# TakpadV5.net
KiCad netlist of a schematic drawn in EAGLE
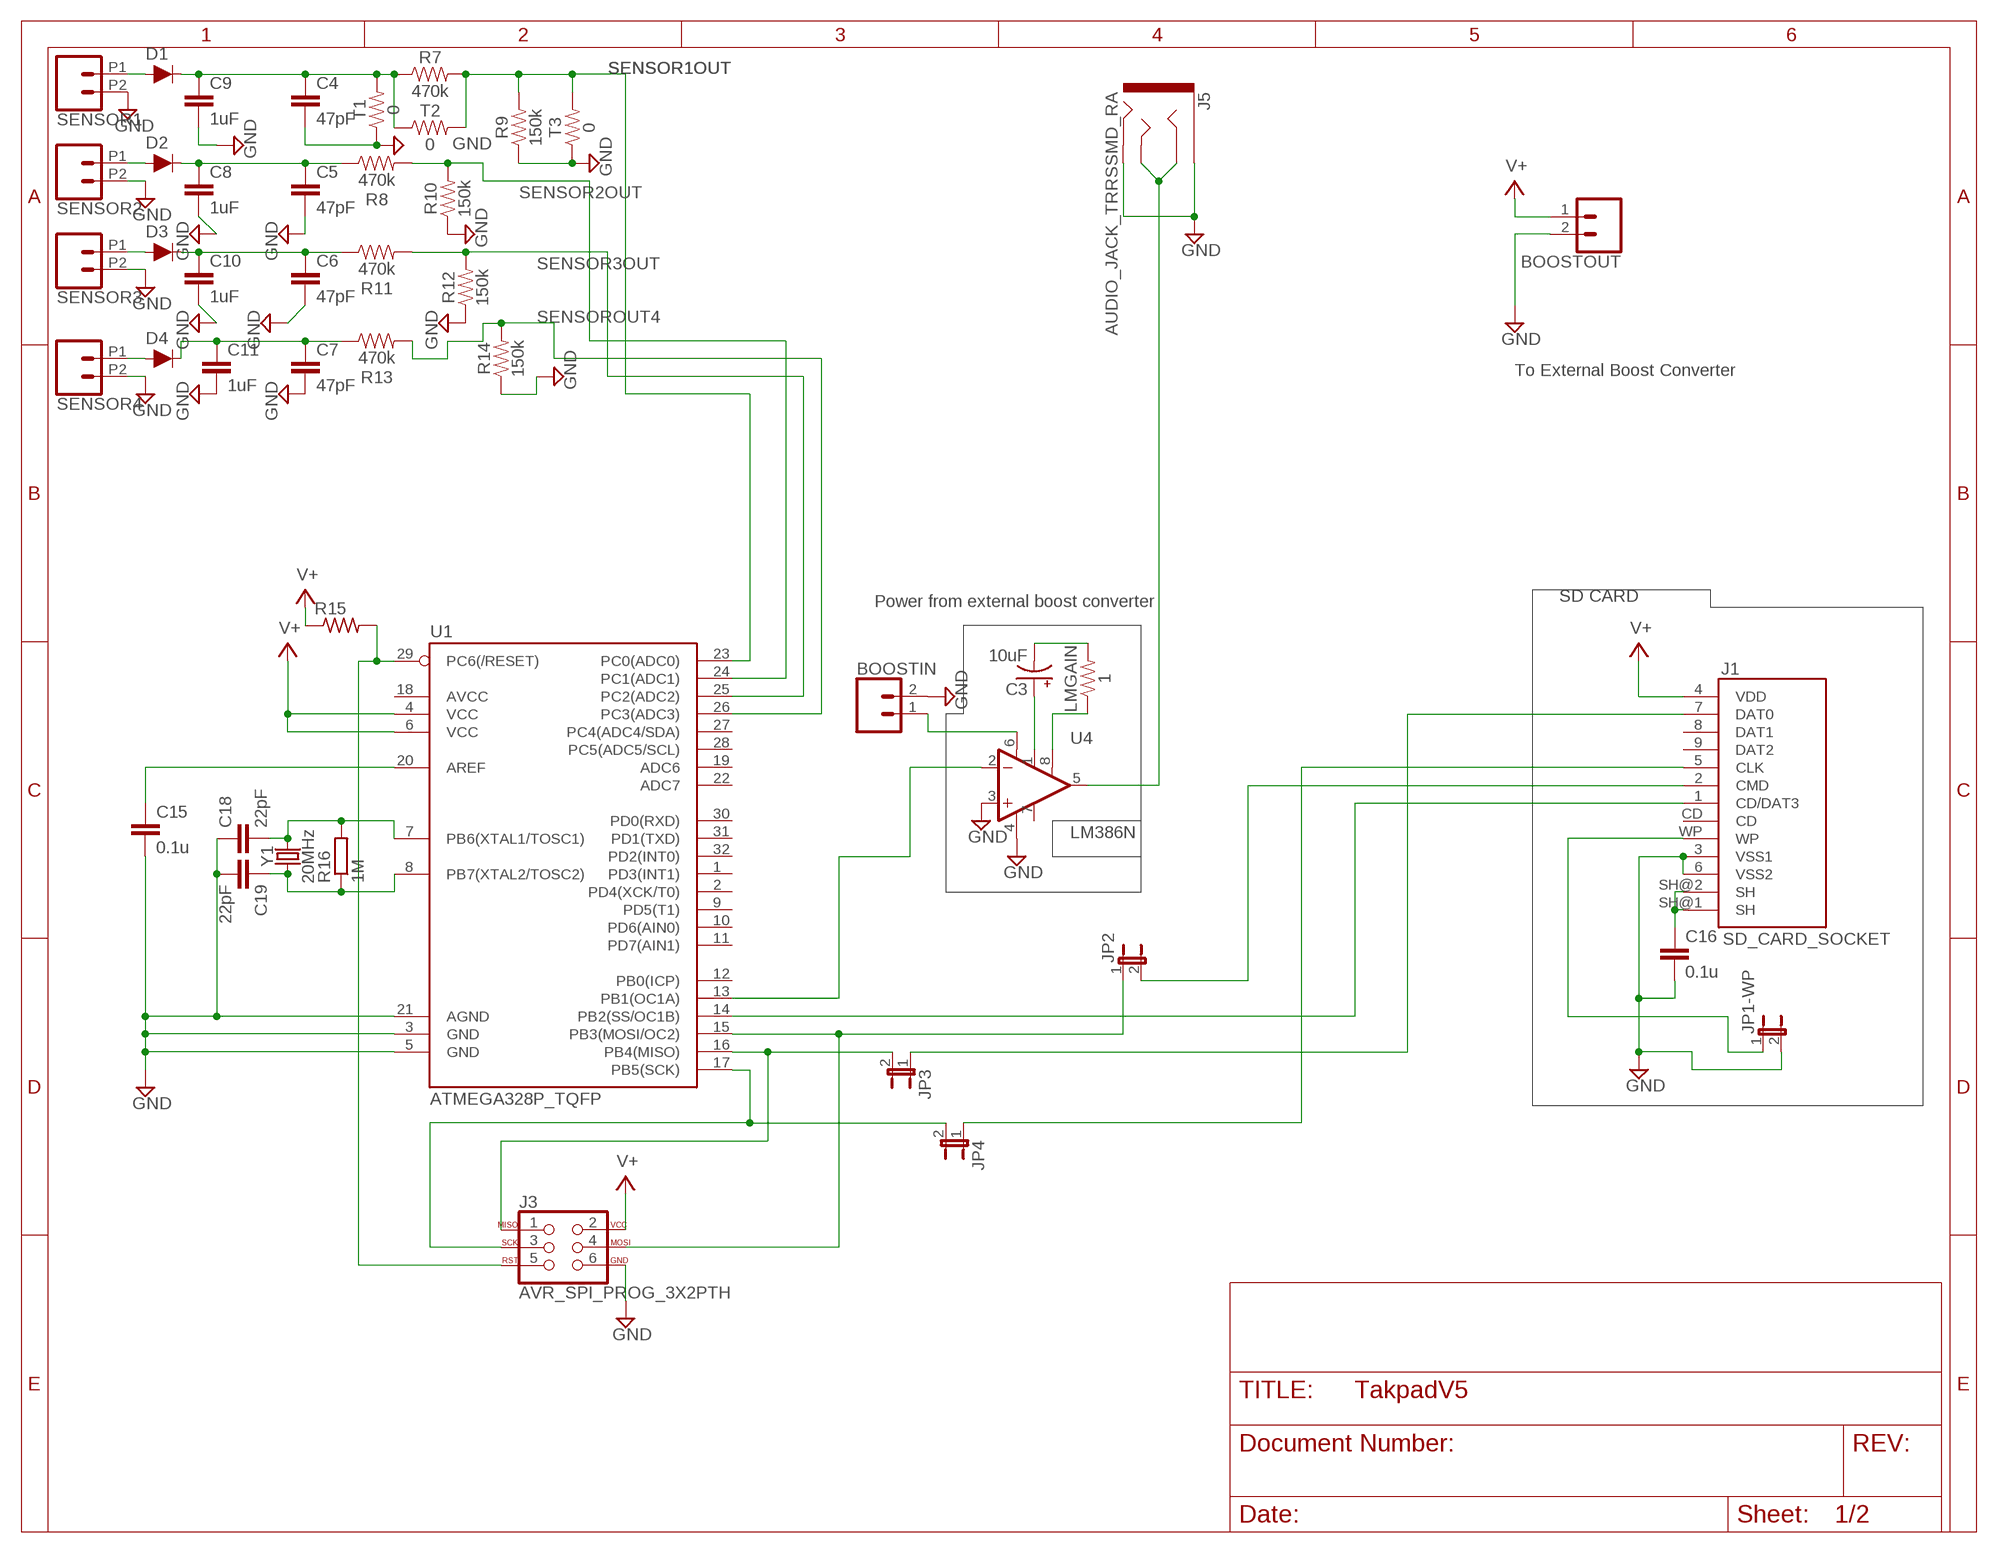
[diagram p0: schematic, sheet 1]
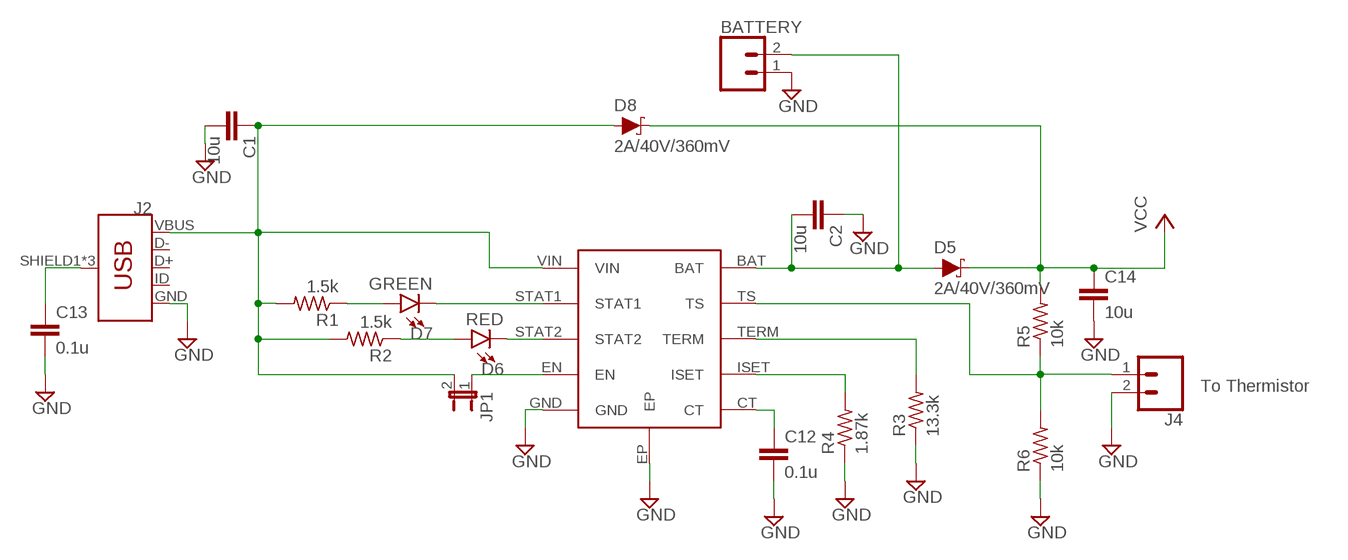
[diagram p1: schematic, sheet 2]

(export (version "E")
  (design (tool "Eeschema 10.0.6"))
  (components
    (comp (ref "BOOSTIN")
      (value "CONN_02")
      (footprint "eagle-import:1X02")
      (libsource (lib "eagle-import") (part "CONN_02"))
    )
    (comp (ref "BOOSTOUT")
      (value "CONN_02")
      (footprint "eagle-import:1X02")
      (libsource (lib "eagle-import") (part "CONN_02"))
    )
    (comp (ref "C3")
      (value "10uF")
      (footprint "eagle-import:CPOL-RADIAL-2.5MM-5MM-KIT")
      (libsource (lib "eagle-import") (part "10UF-POLAR-RADIAL-2.5MM-KIT-25V-20%"))
    )
    (comp (ref "C4")
      (value "47pF")
      (footprint "eagle-import:0603")
      (libsource (lib "eagle-import") (part "47PF-0603-50V-5%"))
    )
    (comp (ref "C5")
      (value "47pF")
      (footprint "eagle-import:0603")
      (libsource (lib "eagle-import") (part "47PF-0603-50V-5%"))
    )
    (comp (ref "C6")
      (value "47pF")
      (footprint "eagle-import:0603")
      (libsource (lib "eagle-import") (part "47PF-0603-50V-5%"))
    )
    (comp (ref "C7")
      (value "47pF")
      (footprint "eagle-import:0603")
      (libsource (lib "eagle-import") (part "47PF-0603-50V-5%"))
    )
    (comp (ref "C8")
      (value "1uF")
      (footprint "eagle-import:0603")
      (libsource (lib "eagle-import") (part "47PF-0603-50V-5%"))
    )
    (comp (ref "C9")
      (value "1uF")
      (footprint "eagle-import:0603")
      (libsource (lib "eagle-import") (part "47PF-0603-50V-5%"))
    )
    (comp (ref "C10")
      (value "1uF")
      (footprint "eagle-import:0603")
      (libsource (lib "eagle-import") (part "47PF-0603-50V-5%"))
    )
    (comp (ref "C11")
      (value "1uF")
      (footprint "eagle-import:0603")
      (libsource (lib "eagle-import") (part "47PF-0603-50V-5%"))
    )
    (comp (ref "C15")
      (value "0.1u")
      (footprint "eagle-import:C0402")
      (libsource (lib "eagle-import") (part "C-EUC0402"))
    )
    (comp (ref "C16")
      (value "0.1u")
      (footprint "eagle-import:C0402")
      (libsource (lib "eagle-import") (part "C-EUC0402"))
    )
    (comp (ref "C18")
      (value "22pF")
      (footprint "eagle-import:C0402")
      (libsource (lib "eagle-import") (part "resistor_348_C-EUC0402"))
    )
    (comp (ref "C19")
      (value "22pF")
      (footprint "eagle-import:C0402")
      (libsource (lib "eagle-import") (part "resistor_348_C-EUC0402"))
    )
    (comp (ref "D1")
      (value "200mA/100V/1V")
      (footprint "eagle-import:DIODE-1N4148")
      (libsource (lib "eagle-import") (part "DIODE-1N4148"))
    )
    (comp (ref "D2")
      (value "200mA/100V/1V")
      (footprint "eagle-import:DIODE-1N4148")
      (libsource (lib "eagle-import") (part "DIODE-1N4148"))
    )
    (comp (ref "D3")
      (value "200mA/100V/1V")
      (footprint "eagle-import:DIODE-1N4148")
      (libsource (lib "eagle-import") (part "DIODE-1N4148"))
    )
    (comp (ref "D4")
      (value "200mA/100V/1V")
      (footprint "eagle-import:DIODE-1N4148")
      (libsource (lib "eagle-import") (part "DIODE-1N4148"))
    )
    (comp (ref "J1")
      (value "SD_CARD_SOCKET")
      (footprint "eagle-import:SD")
      (libsource (lib "eagle-import") (part "SD_CARD_SOCKET"))
    )
    (comp (ref "J3")
      (value "AVR_SPI_PROG_3X2PTH")
      (footprint "eagle-import:2X3")
      (libsource (lib "eagle-import") (part "AVR_SPI_PROG_3X2PTH"))
    )
    (comp (ref "J5")
      (value "AUDIO_JACK_TRRSSMD_RA")
      (footprint "eagle-import:AUDIO_JACK_3.5MM_TRRS_SMD_RA")
      (fields (field (name "SPICEPREFIX") "E"))
      (libsource (lib "eagle-import") (part "AUDIO_JACK_TRRSSMD_RA"))
    )
    (comp (ref "JP1-WP")
      (value "JUMPER-2PTH")
      (footprint "eagle-import:1X02")
      (libsource (lib "eagle-import") (part "JUMPER-2PTH"))
    )
    (comp (ref "JP2")
      (value "JUMPER-2PTH")
      (footprint "eagle-import:1X02")
      (libsource (lib "eagle-import") (part "JUMPER-2PTH"))
    )
    (comp (ref "JP3")
      (value "JUMPER-2PTH")
      (footprint "eagle-import:1X02")
      (libsource (lib "eagle-import") (part "JUMPER-2PTH"))
    )
    (comp (ref "JP4")
      (value "JUMPER-2PTH")
      (footprint "eagle-import:1X02")
      (libsource (lib "eagle-import") (part "JUMPER-2PTH"))
    )
    (comp (ref "LMGAIN")
      (value "1")
      (footprint "eagle-import:0603")
      (libsource (lib "eagle-import") (part "1OHM-0603-1/10W-1%"))
    )
    (comp (ref "R7")
      (value "470k")
      (footprint "eagle-import:AXIAL-0.3")
      (libsource (lib "eagle-import") (part "1KOHM-HORIZ-1/4W-1%"))
    )
    (comp (ref "R8")
      (value "470k")
      (footprint "eagle-import:AXIAL-0.3")
      (libsource (lib "eagle-import") (part "1KOHM-HORIZ-1/4W-1%"))
    )
    (comp (ref "R9")
      (value "150k")
      (footprint "eagle-import:AXIAL-0.3")
      (libsource (lib "eagle-import") (part "1KOHM-HORIZ-1/4W-1%"))
    )
    (comp (ref "R10")
      (value "150k")
      (footprint "eagle-import:AXIAL-0.3")
      (libsource (lib "eagle-import") (part "1KOHM-HORIZ-1/4W-1%"))
    )
    (comp (ref "R11")
      (value "470k")
      (footprint "eagle-import:AXIAL-0.3")
      (libsource (lib "eagle-import") (part "1KOHM-HORIZ-1/4W-1%"))
    )
    (comp (ref "R12")
      (value "150k")
      (footprint "eagle-import:AXIAL-0.3")
      (libsource (lib "eagle-import") (part "1KOHM-HORIZ-1/4W-1%"))
    )
    (comp (ref "R13")
      (value "470k")
      (footprint "eagle-import:AXIAL-0.3")
      (libsource (lib "eagle-import") (part "1KOHM-HORIZ-1/4W-1%"))
    )
    (comp (ref "R14")
      (value "150k")
      (footprint "eagle-import:AXIAL-0.3")
      (libsource (lib "eagle-import") (part "1KOHM-HORIZ-1/4W-1%"))
    )
    (comp (ref "R15")
      (value "R-US_M1206")
      (footprint "eagle-import:M1206")
      (libsource (lib "eagle-import") (part "R-US_M1206"))
    )
    (comp (ref "R16")
      (value "1M")
      (footprint "eagle-import:R0402")
      (libsource (lib "eagle-import") (part "R-EU_R0402"))
    )
    (comp (ref "SENSOR1")
      (value "CONN_022.54MM_SCREWTERM")
      (footprint "eagle-import:1X02_2.54_SCREWTERM")
      (libsource (lib "eagle-import") (part "CONN_022.54MM_SCREWTERM"))
    )
    (comp (ref "SENSOR2")
      (value "CONN_022.54MM_SCREWTERM")
      (footprint "eagle-import:1X02_2.54_SCREWTERM")
      (libsource (lib "eagle-import") (part "CONN_022.54MM_SCREWTERM"))
    )
    (comp (ref "SENSOR3")
      (value "CONN_022.54MM_SCREWTERM")
      (footprint "eagle-import:1X02_2.54_SCREWTERM")
      (libsource (lib "eagle-import") (part "CONN_022.54MM_SCREWTERM"))
    )
    (comp (ref "SENSOR4")
      (value "CONN_022.54MM_SCREWTERM")
      (footprint "eagle-import:1X02_2.54_SCREWTERM")
      (libsource (lib "eagle-import") (part "CONN_022.54MM_SCREWTERM"))
    )
    (comp (ref "T1")
      (value "0")
      (footprint "eagle-import:AXIAL-0.3")
      (libsource (lib "eagle-import") (part "1KOHM-HORIZ-1/4W-1%"))
    )
    (comp (ref "T2")
      (value "0")
      (footprint "eagle-import:AXIAL-0.3")
      (libsource (lib "eagle-import") (part "1KOHM-HORIZ-1/4W-1%"))
    )
    (comp (ref "T3")
      (value "0")
      (footprint "eagle-import:AXIAL-0.3")
      (libsource (lib "eagle-import") (part "1KOHM-HORIZ-1/4W-1%"))
    )
    (comp (ref "U1")
      (value "ATMEGA328P_TQFP")
      (footprint "eagle-import:TQFP32-08")
      (libsource (lib "eagle-import") (part "ATMEGA328P_TQFP"))
    )
    (comp (ref "U4")
      (value "LM386N")
      (footprint "eagle-import:DIP08")
      (libsource (lib "eagle-import") (part "LM386"))
    )
    (comp (ref "Y1")
      (value "20MHz")
      (footprint "eagle-import:HC49US")
      (libsource (lib "eagle-import") (part "CRYSTAL-16MHZPTH-HC49US"))
    )
    (comp (ref "BATTERY")
      (value "CONN_02")
      (footprint "eagle-import:1X02")
      (libsource (lib "eagle-import") (part "CONN_02"))
    )
    (comp (ref "C1")
      (value "10u")
      (footprint "eagle-import:C025-024X044")
      (libsource (lib "eagle-import") (part "C-EU025-024X044"))
    )
    (comp (ref "C2")
      (value "10u")
      (footprint "eagle-import:C025-024X044")
      (libsource (lib "eagle-import") (part "C-EU025-024X044"))
    )
    (comp (ref "C12")
      (value "0.1u")
      (footprint "eagle-import:C0402")
      (libsource (lib "eagle-import") (part "C-EUC0402"))
    )
    (comp (ref "C13")
      (value "0.1u")
      (footprint "eagle-import:C0402")
      (libsource (lib "eagle-import") (part "C-EUC0402"))
    )
    (comp (ref "C14")
      (value "10u")
      (footprint "eagle-import:C025-024X044")
      (libsource (lib "eagle-import") (part "C-EU025-024X044"))
    )
    (comp (ref "D5")
      (value "2A/40V/360mV")
      (footprint "eagle-import:SMA-DIODE")
      (libsource (lib "eagle-import") (part "DIODE-SCHOTTKY-B340A"))
    )
    (comp (ref "D6")
      (value "RED")
      (footprint "eagle-import:LED-1206")
      (libsource (lib "eagle-import") (part "LED-RED1206"))
    )
    (comp (ref "D7")
      (value "GREEN")
      (footprint "eagle-import:LED-1206")
      (libsource (lib "eagle-import") (part "LED-GREEN1206"))
    )
    (comp (ref "D8")
      (value "2A/40V/360mV")
      (footprint "eagle-import:SMA-DIODE")
      (libsource (lib "eagle-import") (part "DIODE-SCHOTTKY-B340A"))
    )
    (comp (ref "J2")
      (value "USB_MICRO-BREDUCED_PASTE")
      (footprint "eagle-import:USB-B-MICRO-SMD_RED_PASTE")
      (libsource (lib "eagle-import") (part "USB_MICRO-BREDUCED_PASTE"))
    )
    (comp (ref "J4")
      (value "CONN_02")
      (footprint "eagle-import:1X02")
      (libsource (lib "eagle-import") (part "CONN_02"))
    )
    (comp (ref "JP1")
      (value "JUMPER-2PTH")
      (footprint "eagle-import:1X02")
      (libsource (lib "eagle-import") (part "JUMPER-2PTH"))
    )
    (comp (ref "R1")
      (value "1.5k")
      (footprint "eagle-import:M1206")
      (libsource (lib "eagle-import") (part "R-US_M1206"))
    )
    (comp (ref "R2")
      (value "1.5k")
      (footprint "eagle-import:M1206")
      (libsource (lib "eagle-import") (part "R-US_M1206"))
    )
    (comp (ref "R3")
      (value "13.3k")
      (footprint "eagle-import:M1206")
      (libsource (lib "eagle-import") (part "R-US_M1206"))
    )
    (comp (ref "R4")
      (value "1.87k")
      (footprint "eagle-import:M1206")
      (libsource (lib "eagle-import") (part "R-US_M1206"))
    )
    (comp (ref "R5")
      (value "10k")
      (footprint "eagle-import:M1206")
      (libsource (lib "eagle-import") (part "R-US_M1206"))
    )
    (comp (ref "R6")
      (value "10k")
      (footprint "eagle-import:M1206")
      (libsource (lib "eagle-import") (part "R-US_M1206"))
    )
    (comp (ref "U$1")
      (value "AAT3693")
      (footprint "eagle-import:IDH-AA-T1")
      (libsource (lib "eagle-import") (part "AAT3693"))
    )
  )
  (nets
    (net (code "1") (name "GND") (class "Default")
      (node (ref "BATTERY") (pin "1") (pinfunction "1_1") (pintype "passive"))
      (node (ref "BOOSTIN") (pin "2") (pinfunction "2_2") (pintype "passive"))
      (node (ref "BOOSTOUT") (pin "2") (pinfunction "2_2") (pintype "passive"))
      (node (ref "C1") (pin "2") (pinfunction "2_2") (pintype "passive"))
      (node (ref "C10") (pin "2") (pinfunction "2_2") (pintype "passive"))
      (node (ref "C11") (pin "2") (pinfunction "2_2") (pintype "passive"))
      (node (ref "C12") (pin "2") (pinfunction "2_2") (pintype "passive"))
      (node (ref "C13") (pin "2") (pinfunction "2_2") (pintype "passive"))
      (node (ref "C14") (pin "2") (pinfunction "2_2") (pintype "passive"))
      (node (ref "C15") (pin "2") (pinfunction "2_2") (pintype "passive"))
      (node (ref "C16") (pin "2") (pinfunction "2_2") (pintype "passive"))
      (node (ref "C18") (pin "1") (pinfunction "1_1") (pintype "passive"))
      (node (ref "C19") (pin "2") (pinfunction "2_2") (pintype "passive"))
      (node (ref "C2") (pin "1") (pinfunction "1_1") (pintype "passive"))
      (node (ref "C4") (pin "2") (pinfunction "2_2") (pintype "passive"))
      (node (ref "C5") (pin "2") (pinfunction "2_2") (pintype "passive"))
      (node (ref "C6") (pin "2") (pinfunction "2_2") (pintype "passive"))
      (node (ref "C7") (pin "2") (pinfunction "2_2") (pintype "passive"))
      (node (ref "C8") (pin "2") (pinfunction "2_2") (pintype "passive"))
      (node (ref "C9") (pin "2") (pinfunction "2_2") (pintype "passive"))
      (node (ref "J1") (pin "3") (pinfunction "VSS1_3") (pintype "power_in"))
      (node (ref "J1") (pin "6") (pinfunction "VSS2_6") (pintype "power_in"))
      (node (ref "J2") (pin "GND") (pinfunction "GND_GND") (pintype "power_in"))
      (node (ref "J3") (pin "6") (pinfunction "6_6") (pintype "passive"))
      (node (ref "J4") (pin "2") (pinfunction "2_2") (pintype "passive"))
      (node (ref "J5") (pin "EARTH") (pinfunction "EARTH_EARTH") (pintype "bidirectional"))
      (node (ref "J5") (pin "RING2") (pinfunction "RING2_RING2") (pintype "bidirectional"))
      (node (ref "JP1-WP") (pin "2") (pinfunction "2_2") (pintype "passive"))
      (node (ref "R10") (pin "P$1") (pinfunction "1_P$1") (pintype "passive"))
      (node (ref "R12") (pin "P$1") (pinfunction "1_P$1") (pintype "passive"))
      (node (ref "R14") (pin "P$1") (pinfunction "1_P$1") (pintype "passive"))
      (node (ref "R3") (pin "1") (pinfunction "1_1") (pintype "passive"))
      (node (ref "R4") (pin "1") (pinfunction "1_1") (pintype "passive"))
      (node (ref "R6") (pin "1") (pinfunction "1_1") (pintype "passive"))
      (node (ref "R9") (pin "P$1") (pinfunction "1_P$1") (pintype "passive"))
      (node (ref "SENSOR1") (pin "P2") (pinfunction "2_P2") (pintype "passive"))
      (node (ref "SENSOR2") (pin "P2") (pinfunction "2_P2") (pintype "passive"))
      (node (ref "SENSOR3") (pin "P2") (pinfunction "2_P2") (pintype "passive"))
      (node (ref "SENSOR4") (pin "P2") (pinfunction "2_P2") (pintype "passive"))
      (node (ref "T1") (pin "P$1") (pinfunction "1_P$1") (pintype "passive"))
      (node (ref "T3") (pin "P$1") (pinfunction "1_P$1") (pintype "passive"))
      (node (ref "U$1") (pin "EP") (pinfunction "EP_EP") (pintype "bidirectional"))
      (node (ref "U$1") (pin "GND") (pinfunction "GND_GND") (pintype "bidirectional"))
      (node (ref "U1") (pin "21") (pinfunction "AGND_21") (pintype "bidirectional"))
      (node (ref "U1") (pin "3") (pinfunction "GND_3") (pintype "bidirectional"))
      (node (ref "U1") (pin "5") (pinfunction "GND_5") (pintype "bidirectional"))
      (node (ref "U4") (pin "3") (pinfunction "+IN_3") (pintype "input"))
      (node (ref "U4") (pin "4") (pinfunction "V-_4") (pintype "power_in"))
    )
    (net (code "2") (name "Net-(BATTERY-Pad2)") (class "Default")
      (node (ref "BATTERY") (pin "2") (pinfunction "2_2") (pintype "passive"))
      (node (ref "C2") (pin "2") (pinfunction "2_2") (pintype "passive"))
      (node (ref "D5") (pin "A") (pinfunction "A_A") (pintype "passive"))
      (node (ref "U$1") (pin "BAT") (pinfunction "BAT_BAT") (pintype "bidirectional"))
    )
    (net (code "3") (name "Net-(C1-Pad1)") (class "Default")
      (node (ref "C1") (pin "1") (pinfunction "1_1") (pintype "passive"))
      (node (ref "D8") (pin "A") (pinfunction "A_A") (pintype "passive"))
      (node (ref "J2") (pin "VBUS") (pinfunction "VBUS_VBUS") (pintype "power_in"))
      (node (ref "JP1") (pin "2") (pinfunction "2_2") (pintype "passive"))
      (node (ref "R1") (pin "2") (pinfunction "2_2") (pintype "passive"))
      (node (ref "R2") (pin "2") (pinfunction "2_2") (pintype "passive"))
      (node (ref "U$1") (pin "VIN") (pinfunction "VIN_VIN") (pintype "bidirectional"))
    )
    (net (code "4") (name "Net-(C3-+)") (class "Default")
      (node (ref "C3") (pin "1") (pinfunction "+_1") (pintype "passive"))
      (node (ref "U4") (pin "1") (pinfunction "GAIN_1") (pintype "bidirectional"))
    )
    (net (code "5") (name "Net-(C3--)") (class "Default")
      (node (ref "C3") (pin "2") (pinfunction "-_2") (pintype "passive"))
      (node (ref "LMGAIN") (pin "2") (pinfunction "2_2") (pintype "passive"))
    )
    (net (code "6") (name "Net-(C12-Pad1)") (class "Default")
      (node (ref "C12") (pin "1") (pinfunction "1_1") (pintype "passive"))
      (node (ref "U$1") (pin "CT") (pinfunction "CT_CT") (pintype "bidirectional"))
    )
    (net (code "7") (name "Net-(C13-Pad1)") (class "Default")
      (node (ref "C13") (pin "1") (pinfunction "1_1") (pintype "passive"))
      (node (ref "J2") (pin "SHIELD1") (pinfunction "SHIELD_SHIELD1") (pintype "bidirectional"))
      (node (ref "J2") (pin "SHIELD2") (pinfunction "SHIELD_SHIELD2") (pintype "bidirectional"))
      (node (ref "J2") (pin "SHIELD3") (pinfunction "SHIELD_SHIELD3") (pintype "bidirectional"))
    )
    (net (code "8") (name "Net-(C16-Pad1)") (class "Default")
      (node (ref "C16") (pin "1") (pinfunction "1_1") (pintype "passive"))
      (node (ref "J1") (pin "SH@1") (pinfunction "SH_SH@1") (pintype "bidirectional"))
      (node (ref "J1") (pin "SH@2") (pinfunction "SH_SH@2") (pintype "bidirectional"))
    )
    (net (code "9") (name "Net-(D6-PadA)") (class "Default")
      (node (ref "D6") (pin "A") (pinfunction "A_A") (pintype "passive"))
      (node (ref "R2") (pin "1") (pinfunction "1_1") (pintype "passive"))
    )
    (net (code "10") (name "Net-(D6-PadC)") (class "Default")
      (node (ref "D6") (pin "C") (pinfunction "C_C") (pintype "passive"))
      (node (ref "U$1") (pin "STAT2") (pinfunction "STAT2_STAT2") (pintype "bidirectional"))
    )
    (net (code "11") (name "Net-(D7-PadA)") (class "Default")
      (node (ref "D7") (pin "A") (pinfunction "A_A") (pintype "passive"))
      (node (ref "R1") (pin "1") (pinfunction "1_1") (pintype "passive"))
    )
    (net (code "12") (name "Net-(D7-PadC)") (class "Default")
      (node (ref "D7") (pin "C") (pinfunction "C_C") (pintype "passive"))
      (node (ref "U$1") (pin "STAT1") (pinfunction "STAT1_STAT1") (pintype "bidirectional"))
    )
    (net (code "13") (name "Net-(J1-CD{slash}DAT3)") (class "Default")
      (node (ref "J1") (pin "1") (pinfunction "CD/DAT3_1") (pintype "bidirectional"))
      (node (ref "U1") (pin "14") (pinfunction "PB2(SS/OC1B)_14") (pintype "bidirectional"))
    )
    (net (code "14") (name "Net-(J1-CLK)") (class "Default")
      (node (ref "J1") (pin "5") (pinfunction "CLK_5") (pintype "bidirectional"))
      (node (ref "JP4") (pin "1") (pinfunction "1_1") (pintype "passive"))
    )
    (net (code "15") (name "Net-(J1-CMD)") (class "Default")
      (node (ref "J1") (pin "2") (pinfunction "CMD_2") (pintype "bidirectional"))
      (node (ref "JP2") (pin "2") (pinfunction "2_2") (pintype "passive"))
    )
    (net (code "16") (name "Net-(J1-DAT0)") (class "Default")
      (node (ref "J1") (pin "7") (pinfunction "DAT0_7") (pintype "bidirectional"))
      (node (ref "JP3") (pin "1") (pinfunction "1_1") (pintype "passive"))
    )
    (net (code "17") (name "Net-(J1-PadWP)") (class "Default")
      (node (ref "J1") (pin "WP") (pinfunction "WP_WP") (pintype "bidirectional"))
      (node (ref "JP1-WP") (pin "1") (pinfunction "1_1") (pintype "passive"))
    )
    (net (code "18") (name "Net-(J4-Pad1)") (class "Default")
      (node (ref "J4") (pin "1") (pinfunction "1_1") (pintype "passive"))
      (node (ref "R5") (pin "1") (pinfunction "1_1") (pintype "passive"))
      (node (ref "R6") (pin "2") (pinfunction "2_2") (pintype "passive"))
      (node (ref "U$1") (pin "TS") (pinfunction "TS_TS") (pintype "bidirectional"))
    )
    (net (code "19") (name "Net-(JP1-Pad1)") (class "Default")
      (node (ref "JP1") (pin "1") (pinfunction "1_1") (pintype "passive"))
      (node (ref "U$1") (pin "EN") (pinfunction "EN_EN") (pintype "bidirectional"))
    )
    (net (code "20") (name "Net-(LMGAIN-Pad1)") (class "Default")
      (node (ref "LMGAIN") (pin "1") (pinfunction "1_1") (pintype "passive"))
      (node (ref "U4") (pin "8") (pinfunction "GAIN_8") (pintype "bidirectional"))
    )
    (net (code "21") (name "Net-(R3-Pad2)") (class "Default")
      (node (ref "R3") (pin "2") (pinfunction "2_2") (pintype "passive"))
      (node (ref "U$1") (pin "TERM") (pinfunction "TERM_TERM") (pintype "bidirectional"))
    )
    (net (code "22") (name "Net-(R4-Pad2)") (class "Default")
      (node (ref "R4") (pin "2") (pinfunction "2_2") (pintype "passive"))
      (node (ref "U$1") (pin "ISET") (pinfunction "ISET_ISET") (pintype "bidirectional"))
    )
    (net (code "23") (name "Net-(R7-1)") (class "Default")
      (node (ref "C4") (pin "1") (pinfunction "1_1") (pintype "passive"))
      (node (ref "C9") (pin "1") (pinfunction "1_1") (pintype "passive"))
      (node (ref "D1") (pin "C") (pinfunction "C_C") (pintype "passive"))
      (node (ref "R7") (pin "P$1") (pinfunction "1_P$1") (pintype "passive"))
      (node (ref "T1") (pin "P$2") (pinfunction "2_P$2") (pintype "passive"))
      (node (ref "T2") (pin "P$1") (pinfunction "1_P$1") (pintype "passive"))
    )
    (net (code "24") (name "Net-(R8-1)") (class "Default")
      (node (ref "C5") (pin "1") (pinfunction "1_1") (pintype "passive"))
      (node (ref "C8") (pin "1") (pinfunction "1_1") (pintype "passive"))
      (node (ref "D2") (pin "C") (pinfunction "C_C") (pintype "passive"))
      (node (ref "R8") (pin "P$1") (pinfunction "1_P$1") (pintype "passive"))
    )
    (net (code "25") (name "Net-(R11-1)") (class "Default")
      (node (ref "C10") (pin "1") (pinfunction "1_1") (pintype "passive"))
      (node (ref "C6") (pin "1") (pinfunction "1_1") (pintype "passive"))
      (node (ref "D3") (pin "C") (pinfunction "C_C") (pintype "passive"))
      (node (ref "R11") (pin "P$1") (pinfunction "1_P$1") (pintype "passive"))
    )
    (net (code "26") (name "Net-(R13-1)") (class "Default")
      (node (ref "C11") (pin "1") (pinfunction "1_1") (pintype "passive"))
      (node (ref "C7") (pin "1") (pinfunction "1_1") (pintype "passive"))
      (node (ref "D4") (pin "C") (pinfunction "C_C") (pintype "passive"))
      (node (ref "R13") (pin "P$1") (pinfunction "1_P$1") (pintype "passive"))
    )
    (net (code "27") (name "Net-(SENSOR1-1)") (class "Default")
      (node (ref "D1") (pin "A") (pinfunction "A_A") (pintype "passive"))
      (node (ref "SENSOR1") (pin "P1") (pinfunction "1_P1") (pintype "passive"))
    )
    (net (code "28") (name "Net-(SENSOR2-1)") (class "Default")
      (node (ref "D2") (pin "A") (pinfunction "A_A") (pintype "passive"))
      (node (ref "SENSOR2") (pin "P1") (pinfunction "1_P1") (pintype "passive"))
    )
    (net (code "29") (name "Net-(SENSOR3-1)") (class "Default")
      (node (ref "D3") (pin "A") (pinfunction "A_A") (pintype "passive"))
      (node (ref "SENSOR3") (pin "P1") (pinfunction "1_P1") (pintype "passive"))
    )
    (net (code "30") (name "Net-(SENSOR4-1)") (class "Default")
      (node (ref "D4") (pin "A") (pinfunction "A_A") (pintype "passive"))
      (node (ref "SENSOR4") (pin "P1") (pinfunction "1_P1") (pintype "passive"))
    )
    (net (code "31") (name "Net-(U1-AREF)") (class "Default")
      (node (ref "C15") (pin "1") (pinfunction "1_1") (pintype "passive"))
      (node (ref "U1") (pin "20") (pinfunction "AREF_20") (pintype "bidirectional"))
    )
    (net (code "32") (name "Net-(U1-PB1(OC1A))") (class "Default")
      (node (ref "U1") (pin "13") (pinfunction "PB1(OC1A)_13") (pintype "bidirectional"))
      (node (ref "U4") (pin "2") (pinfunction "-IN_2") (pintype "input"))
    )
    (net (code "33") (name "Net-(U1-PB3(MOSI{slash}OC2))") (class "Default")
      (node (ref "J3") (pin "4") (pinfunction "4_4") (pintype "passive"))
      (node (ref "JP2") (pin "1") (pinfunction "1_1") (pintype "passive"))
      (node (ref "U1") (pin "15") (pinfunction "PB3(MOSI/OC2)_15") (pintype "bidirectional"))
    )
    (net (code "34") (name "Net-(U1-PB4(MISO))") (class "Default")
      (node (ref "J3") (pin "1") (pinfunction "1_1") (pintype "passive"))
      (node (ref "JP3") (pin "2") (pinfunction "2_2") (pintype "passive"))
      (node (ref "U1") (pin "16") (pinfunction "PB4(MISO)_16") (pintype "bidirectional"))
    )
    (net (code "35") (name "Net-(U1-PB5(SCK))") (class "Default")
      (node (ref "J3") (pin "3") (pinfunction "3_3") (pintype "passive"))
      (node (ref "JP4") (pin "2") (pinfunction "2_2") (pintype "passive"))
      (node (ref "U1") (pin "17") (pinfunction "PB5(SCK)_17") (pintype "bidirectional"))
    )
    (net (code "36") (name "Net-(U1-PB6(XTAL1{slash}TOSC1))") (class "Default")
      (node (ref "C18") (pin "2") (pinfunction "2_2") (pintype "passive"))
      (node (ref "R16") (pin "2") (pinfunction "2_2") (pintype "passive"))
      (node (ref "U1") (pin "7") (pinfunction "PB6(XTAL1/TOSC1)_7") (pintype "bidirectional"))
      (node (ref "Y1") (pin "2") (pinfunction "2_2") (pintype "passive"))
    )
    (net (code "37") (name "Net-(U1-PB7(XTAL2{slash}TOSC2))") (class "Default")
      (node (ref "C19") (pin "1") (pinfunction "1_1") (pintype "passive"))
      (node (ref "R16") (pin "1") (pinfunction "1_1") (pintype "passive"))
      (node (ref "U1") (pin "8") (pinfunction "PB7(XTAL2/TOSC2)_8") (pintype "bidirectional"))
      (node (ref "Y1") (pin "1") (pinfunction "1_1") (pintype "passive"))
    )
    (net (code "38") (name "Net-(U1-PC6({slash}RESET))") (class "Default")
      (node (ref "J3") (pin "5") (pinfunction "5_5") (pintype "passive"))
      (node (ref "R15") (pin "2") (pinfunction "2_2") (pintype "passive"))
      (node (ref "U1") (pin "29") (pinfunction "PC6(/RESET)_29") (pintype "bidirectional"))
    )
    (net (code "39") (name "Net-(U4-OUT)") (class "Default")
      (node (ref "J5") (pin "RING1") (pinfunction "RING1_RING1") (pintype "bidirectional"))
      (node (ref "J5") (pin "TIP") (pinfunction "TIP_TIP") (pintype "bidirectional"))
      (node (ref "U4") (pin "5") (pinfunction "OUT_5") (pintype "output"))
    )
    (net (code "40") (name "Net-(U4-V+)") (class "Default")
      (node (ref "BOOSTIN") (pin "1") (pinfunction "1_1") (pintype "passive"))
      (node (ref "U4") (pin "6") (pinfunction "V+_6") (pintype "power_in"))
    )
    (net (code "41") (name "SENSOR1OUT") (class "Default")
      (node (ref "R7") (pin "P$2") (pinfunction "2_P$2") (pintype "passive"))
      (node (ref "R9") (pin "P$2") (pinfunction "2_P$2") (pintype "passive"))
      (node (ref "T2") (pin "P$2") (pinfunction "2_P$2") (pintype "passive"))
      (node (ref "T3") (pin "P$2") (pinfunction "2_P$2") (pintype "passive"))
      (node (ref "U1") (pin "23") (pinfunction "PC0(ADC0)_23") (pintype "bidirectional"))
    )
    (net (code "42") (name "SENSOR2OUT") (class "Default")
      (node (ref "R10") (pin "P$2") (pinfunction "2_P$2") (pintype "passive"))
      (node (ref "R8") (pin "P$2") (pinfunction "2_P$2") (pintype "passive"))
      (node (ref "U1") (pin "24") (pinfunction "PC1(ADC1)_24") (pintype "bidirectional"))
    )
    (net (code "43") (name "SENSOR3OUT") (class "Default")
      (node (ref "R11") (pin "P$2") (pinfunction "2_P$2") (pintype "passive"))
      (node (ref "R12") (pin "P$2") (pinfunction "2_P$2") (pintype "passive"))
      (node (ref "U1") (pin "25") (pinfunction "PC2(ADC2)_25") (pintype "bidirectional"))
    )
    (net (code "44") (name "SENSOROUT4") (class "Default")
      (node (ref "R13") (pin "P$2") (pinfunction "2_P$2") (pintype "passive"))
      (node (ref "R14") (pin "P$2") (pinfunction "2_P$2") (pintype "passive"))
      (node (ref "U1") (pin "26") (pinfunction "PC3(ADC3)_26") (pintype "bidirectional"))
    )
    (net (code "45") (name "V+") (class "Default")
      (node (ref "BOOSTOUT") (pin "1") (pinfunction "1_1") (pintype "passive"))
      (node (ref "J1") (pin "4") (pinfunction "VDD_4") (pintype "power_in"))
      (node (ref "J3") (pin "2") (pinfunction "2_2") (pintype "passive"))
      (node (ref "R15") (pin "1") (pinfunction "1_1") (pintype "passive"))
      (node (ref "U1") (pin "4") (pinfunction "VCC_4") (pintype "bidirectional"))
      (node (ref "U1") (pin "6") (pinfunction "VCC_6") (pintype "bidirectional"))
    )
    (net (code "46") (name "VCC") (class "Default")
      (node (ref "C14") (pin "1") (pinfunction "1_1") (pintype "passive"))
      (node (ref "D5") (pin "C") (pinfunction "C_C") (pintype "passive"))
      (node (ref "D8") (pin "C") (pinfunction "C_C") (pintype "passive"))
      (node (ref "R5") (pin "2") (pinfunction "2_2") (pintype "passive"))
    )
    (net (code "47") (name "unconnected-(J1-DAT1-Pad8)") (class "Default")
      (node (ref "J1") (pin "8") (pinfunction "DAT1_8") (pintype "bidirectional"))
    )
    (net (code "48") (name "unconnected-(J1-DAT2-Pad9)") (class "Default")
      (node (ref "J1") (pin "9") (pinfunction "DAT2_9") (pintype "bidirectional"))
    )
    (net (code "49") (name "unconnected-(J1-PadCD)") (class "Default")
      (node (ref "J1") (pin "CD") (pinfunction "CD_CD") (pintype "bidirectional"))
    )
    (net (code "50") (name "unconnected-(J2-PadD+)") (class "Default")
      (node (ref "J2") (pin "D+") (pinfunction "D+_D+") (pintype "bidirectional"))
    )
    (net (code "51") (name "unconnected-(J2-PadD-)") (class "Default")
      (node (ref "J2") (pin "D-") (pinfunction "D-_D-") (pintype "bidirectional"))
    )
    (net (code "52") (name "unconnected-(J2-PadID)") (class "Default")
      (node (ref "J2") (pin "ID") (pinfunction "ID_ID") (pintype "bidirectional"))
    )
    (net (code "53") (name "unconnected-(U1-ADC6-Pad19)") (class "Default")
      (node (ref "U1") (pin "19") (pinfunction "ADC6_19") (pintype "bidirectional"))
    )
    (net (code "54") (name "unconnected-(U1-ADC7-Pad22)") (class "Default")
      (node (ref "U1") (pin "22") (pinfunction "ADC7_22") (pintype "bidirectional"))
    )
    (net (code "55") (name "unconnected-(U1-AVCC-Pad18)") (class "Default")
      (node (ref "U1") (pin "18") (pinfunction "AVCC_18") (pintype "bidirectional"))
    )
    (net (code "56") (name "unconnected-(U1-PB0(ICP)-Pad12)") (class "Default")
      (node (ref "U1") (pin "12") (pinfunction "PB0(ICP)_12") (pintype "bidirectional"))
    )
    (net (code "57") (name "unconnected-(U1-PC4(ADC4{slash}SDA)-Pad27)") (class "Default")
      (node (ref "U1") (pin "27") (pinfunction "PC4(ADC4/SDA)_27") (pintype "bidirectional"))
    )
    (net (code "58") (name "unconnected-(U1-PC5(ADC5{slash}SCL)-Pad28)") (class "Default")
      (node (ref "U1") (pin "28") (pinfunction "PC5(ADC5/SCL)_28") (pintype "bidirectional"))
    )
    (net (code "59") (name "unconnected-(U1-PD0(RXD)-Pad30)") (class "Default")
      (node (ref "U1") (pin "30") (pinfunction "PD0(RXD)_30") (pintype "bidirectional"))
    )
    (net (code "60") (name "unconnected-(U1-PD1(TXD)-Pad31)") (class "Default")
      (node (ref "U1") (pin "31") (pinfunction "PD1(TXD)_31") (pintype "bidirectional"))
    )
    (net (code "61") (name "unconnected-(U1-PD2(INT0)-Pad32)") (class "Default")
      (node (ref "U1") (pin "32") (pinfunction "PD2(INT0)_32") (pintype "bidirectional"))
    )
    (net (code "62") (name "unconnected-(U1-PD3(INT1)-Pad1)") (class "Default")
      (node (ref "U1") (pin "1") (pinfunction "PD3(INT1)_1") (pintype "bidirectional"))
    )
    (net (code "63") (name "unconnected-(U1-PD4(XCK{slash}T0)-Pad2)") (class "Default")
      (node (ref "U1") (pin "2") (pinfunction "PD4(XCK/T0)_2") (pintype "bidirectional"))
    )
    (net (code "64") (name "unconnected-(U1-PD5(T1)-Pad9)") (class "Default")
      (node (ref "U1") (pin "9") (pinfunction "PD5(T1)_9") (pintype "bidirectional"))
    )
    (net (code "65") (name "unconnected-(U1-PD6(AIN0)-Pad10)") (class "Default")
      (node (ref "U1") (pin "10") (pinfunction "PD6(AIN0)_10") (pintype "bidirectional"))
    )
    (net (code "66") (name "unconnected-(U1-PD7(AIN1)-Pad11)") (class "Default")
      (node (ref "U1") (pin "11") (pinfunction "PD7(AIN1)_11") (pintype "bidirectional"))
    )
    (net (code "67") (name "unconnected-(U4-BP-Pad7)") (class "Default")
      (node (ref "U4") (pin "7") (pinfunction "BP_7") (pintype "bidirectional"))
    )
  )
)
